# Charge_Deck.net
KiCad netlist of a schematic drawn in Altium Designer
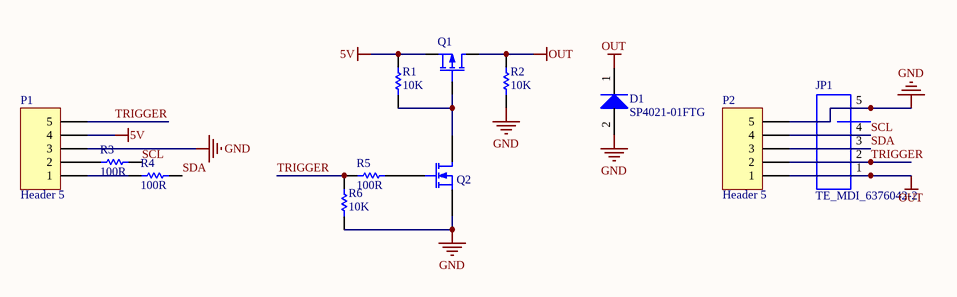
[diagram p0: Charge_Deck.SchDoc]

(export (version "E")
  (design (tool "Eeschema 10.0.6"))
  (components
    (comp (ref "D1")
      (value "SP4021-01FTG")
      (footprint "SOD-323")
      (fields (field (name "MANUFACTURER") "Littelfuse"))
      (libsource (lib "Diodes") (part "SP4021-01FTG"))
    )
    (comp (ref "JP1")
      (value "TE_MDI_6376042-2")
      (footprint "TE_6376042-2")
      (description "BLADE CONNECTOR, 5 PIN, MALE, HORIZ")
      (fields (field (name "PARTNUMBER") "6376042-2") (field (name "MANUFACTURER") "TE Connectivity"))
      (libsource (lib "Connectors") (part "TE_MDI_6376042-2"))
    )
    (comp (ref "P1")
      (value "Header 5")
      (footprint "HDR1X5")
      (description "Header, 5-Pin")
      (fields (field (name "PUBLISHER") "Altium Limited"))
      (libsource (lib "Miscellaneous Connectors") (part "Header 5"))
    )
    (comp (ref "P2")
      (value "Header 5")
      (footprint "HDR1X5")
      (description "Header, 5-Pin")
      (fields (field (name "PUBLISHER") "Altium Limited"))
      (libsource (lib "Miscellaneous Connectors") (part "Header 5"))
    )
    (comp (ref "Q1")
      (value "SI2309CDS-T1-GE3")
      (footprint "SOT23-3")
      (description "P-Channel MOSFET")
      (fields (field (name "MANUFACTURER") "Vishay"))
      (libsource (lib "MOSFETs") (part "SI2309CDS-T1-GE3"))
    )
    (comp (ref "Q2")
      (value "BSS123WQ-7-F")
      (footprint "SOT323-3")
      (description "N-Channel MOSFET")
      (fields (field (name "MANUFACTURER") "Diodes Incorporated"))
      (libsource (lib "MOSFETs") (part "BSS123WQ-7-F"))
    )
    (comp (ref "R1")
      (value "10K")
      (footprint "R0603[1608]")
      (description "10K 0.25W 1% 0603 (1005 Metric)")
      (fields (field (name "POWER") "0.25W") (field (name "TOLERANCE") "1%"))
      (libsource (lib "Resistors") (part "RES_10K_0603_1%"))
    )
    (comp (ref "R2")
      (value "10K")
      (footprint "R0603[1608]")
      (description "10K 0.25W 1% 0603 (1005 Metric)")
      (fields (field (name "POWER") "0.25W") (field (name "TOLERANCE") "1%"))
      (libsource (lib "Resistors") (part "RES_10K_0603_1%"))
    )
    (comp (ref "R3")
      (value "100R")
      (footprint "R0603[1608]")
      (description "100R 0.25W 1% 0603 (1005 Metric)")
      (fields (field (name "MANUFACTURER") "Vishay / Dale") (field (name "PARTNUMBER") "CRCW0603100RFKEAHP"))
      (libsource (lib "Resistors") (part "RES_100R_0603_1%"))
    )
    (comp (ref "R4")
      (value "100R")
      (footprint "R0603[1608]")
      (description "100R 0.25W 1% 0603 (1005 Metric)")
      (fields (field (name "MANUFACTURER") "Vishay / Dale") (field (name "PARTNUMBER") "CRCW0603100RFKEAHP"))
      (libsource (lib "Resistors") (part "RES_100R_0603_1%"))
    )
    (comp (ref "R5")
      (value "100R")
      (footprint "R0603[1608]")
      (description "100R 0.25W 1% 0603 (1005 Metric)")
      (fields (field (name "MANUFACTURER") "Vishay / Dale") (field (name "PARTNUMBER") "CRCW0603100RFKEAHP"))
      (libsource (lib "Resistors") (part "RES_100R_0603_1%"))
    )
    (comp (ref "R6")
      (value "10K")
      (footprint "R0603[1608]")
      (description "10K 0.25W 1% 0603 (1005 Metric)")
      (fields (field (name "POWER") "0.25W") (field (name "TOLERANCE") "1%"))
      (libsource (lib "Resistors") (part "RES_10K_0603_1%"))
    )
  )
  (nets
    (net (code "1") (name "/SCL") (class "Default")
      (node (ref "JP1") (pin "4") (pinfunction "4_4") (pintype "passive"))
      (node (ref "P2") (pin "4") (pinfunction "4_4") (pintype "passive"))
      (node (ref "R3") (pin "1") (pinfunction "1_1") (pintype "passive"))
    )
    (net (code "2") (name "/SDA") (class "Default")
      (node (ref "JP1") (pin "3") (pinfunction "3_3") (pintype "passive"))
      (node (ref "P2") (pin "3") (pinfunction "3_3") (pintype "passive"))
      (node (ref "R4") (pin "1") (pinfunction "1_1") (pintype "passive"))
    )
    (net (code "3") (name "/TRIGGER") (class "Default")
      (node (ref "JP1") (pin "2") (pinfunction "2_2") (pintype "passive"))
      (node (ref "P1") (pin "5") (pinfunction "5_5") (pintype "passive"))
      (node (ref "P2") (pin "2") (pinfunction "2_2") (pintype "passive"))
      (node (ref "R5") (pin "2") (pinfunction "2_2") (pintype "passive"))
      (node (ref "R6") (pin "2") (pinfunction "2_2") (pintype "passive"))
    )
    (net (code "4") (name "5V") (class "Default")
      (node (ref "P1") (pin "4") (pinfunction "4_4") (pintype "passive"))
      (node (ref "Q1") (pin "3") (pinfunction "S_3") (pintype "passive"))
      (node (ref "R1") (pin "2") (pinfunction "2_2") (pintype "passive"))
    )
    (net (code "5") (name "GND") (class "Default")
      (node (ref "D1") (pin "2") (pinfunction "A_2") (pintype "passive"))
      (node (ref "JP1") (pin "5") (pinfunction "5_5") (pintype "passive"))
      (node (ref "P1") (pin "3") (pinfunction "3_3") (pintype "passive"))
      (node (ref "P2") (pin "5") (pinfunction "5_5") (pintype "passive"))
      (node (ref "Q2") (pin "2") (pinfunction "S_2") (pintype "passive"))
      (node (ref "R2") (pin "1") (pinfunction "1_1") (pintype "passive"))
      (node (ref "R6") (pin "1") (pinfunction "1_1") (pintype "passive"))
    )
    (net (code "6") (name "Net-(P1-Pad1)") (class "Default")
      (node (ref "P1") (pin "1") (pinfunction "1_1") (pintype "passive"))
      (node (ref "R4") (pin "2") (pinfunction "2_2") (pintype "passive"))
    )
    (net (code "7") (name "Net-(P1-Pad2)") (class "Default")
      (node (ref "P1") (pin "2") (pinfunction "2_2") (pintype "passive"))
      (node (ref "R3") (pin "2") (pinfunction "2_2") (pintype "passive"))
    )
    (net (code "8") (name "Net-(Q1-G)") (class "Default")
      (node (ref "Q1") (pin "1") (pinfunction "G_1") (pintype "passive"))
      (node (ref "Q2") (pin "3") (pinfunction "D_3") (pintype "passive"))
      (node (ref "R1") (pin "1") (pinfunction "1_1") (pintype "passive"))
    )
    (net (code "9") (name "Net-(Q2-G)") (class "Default")
      (node (ref "Q2") (pin "1") (pinfunction "G_1") (pintype "passive"))
      (node (ref "R5") (pin "1") (pinfunction "1_1") (pintype "passive"))
    )
    (net (code "10") (name "OUT") (class "Default")
      (node (ref "D1") (pin "1") (pinfunction "K_1") (pintype "passive"))
      (node (ref "JP1") (pin "1") (pinfunction "1_1") (pintype "passive"))
      (node (ref "P2") (pin "1") (pinfunction "1_1") (pintype "passive"))
      (node (ref "Q1") (pin "2") (pinfunction "D_2") (pintype "passive"))
      (node (ref "R2") (pin "2") (pinfunction "2_2") (pintype "passive"))
    )
  )
)
